# EasyEDA.net
KiCad netlist of a schematic drawn in EasyEDA
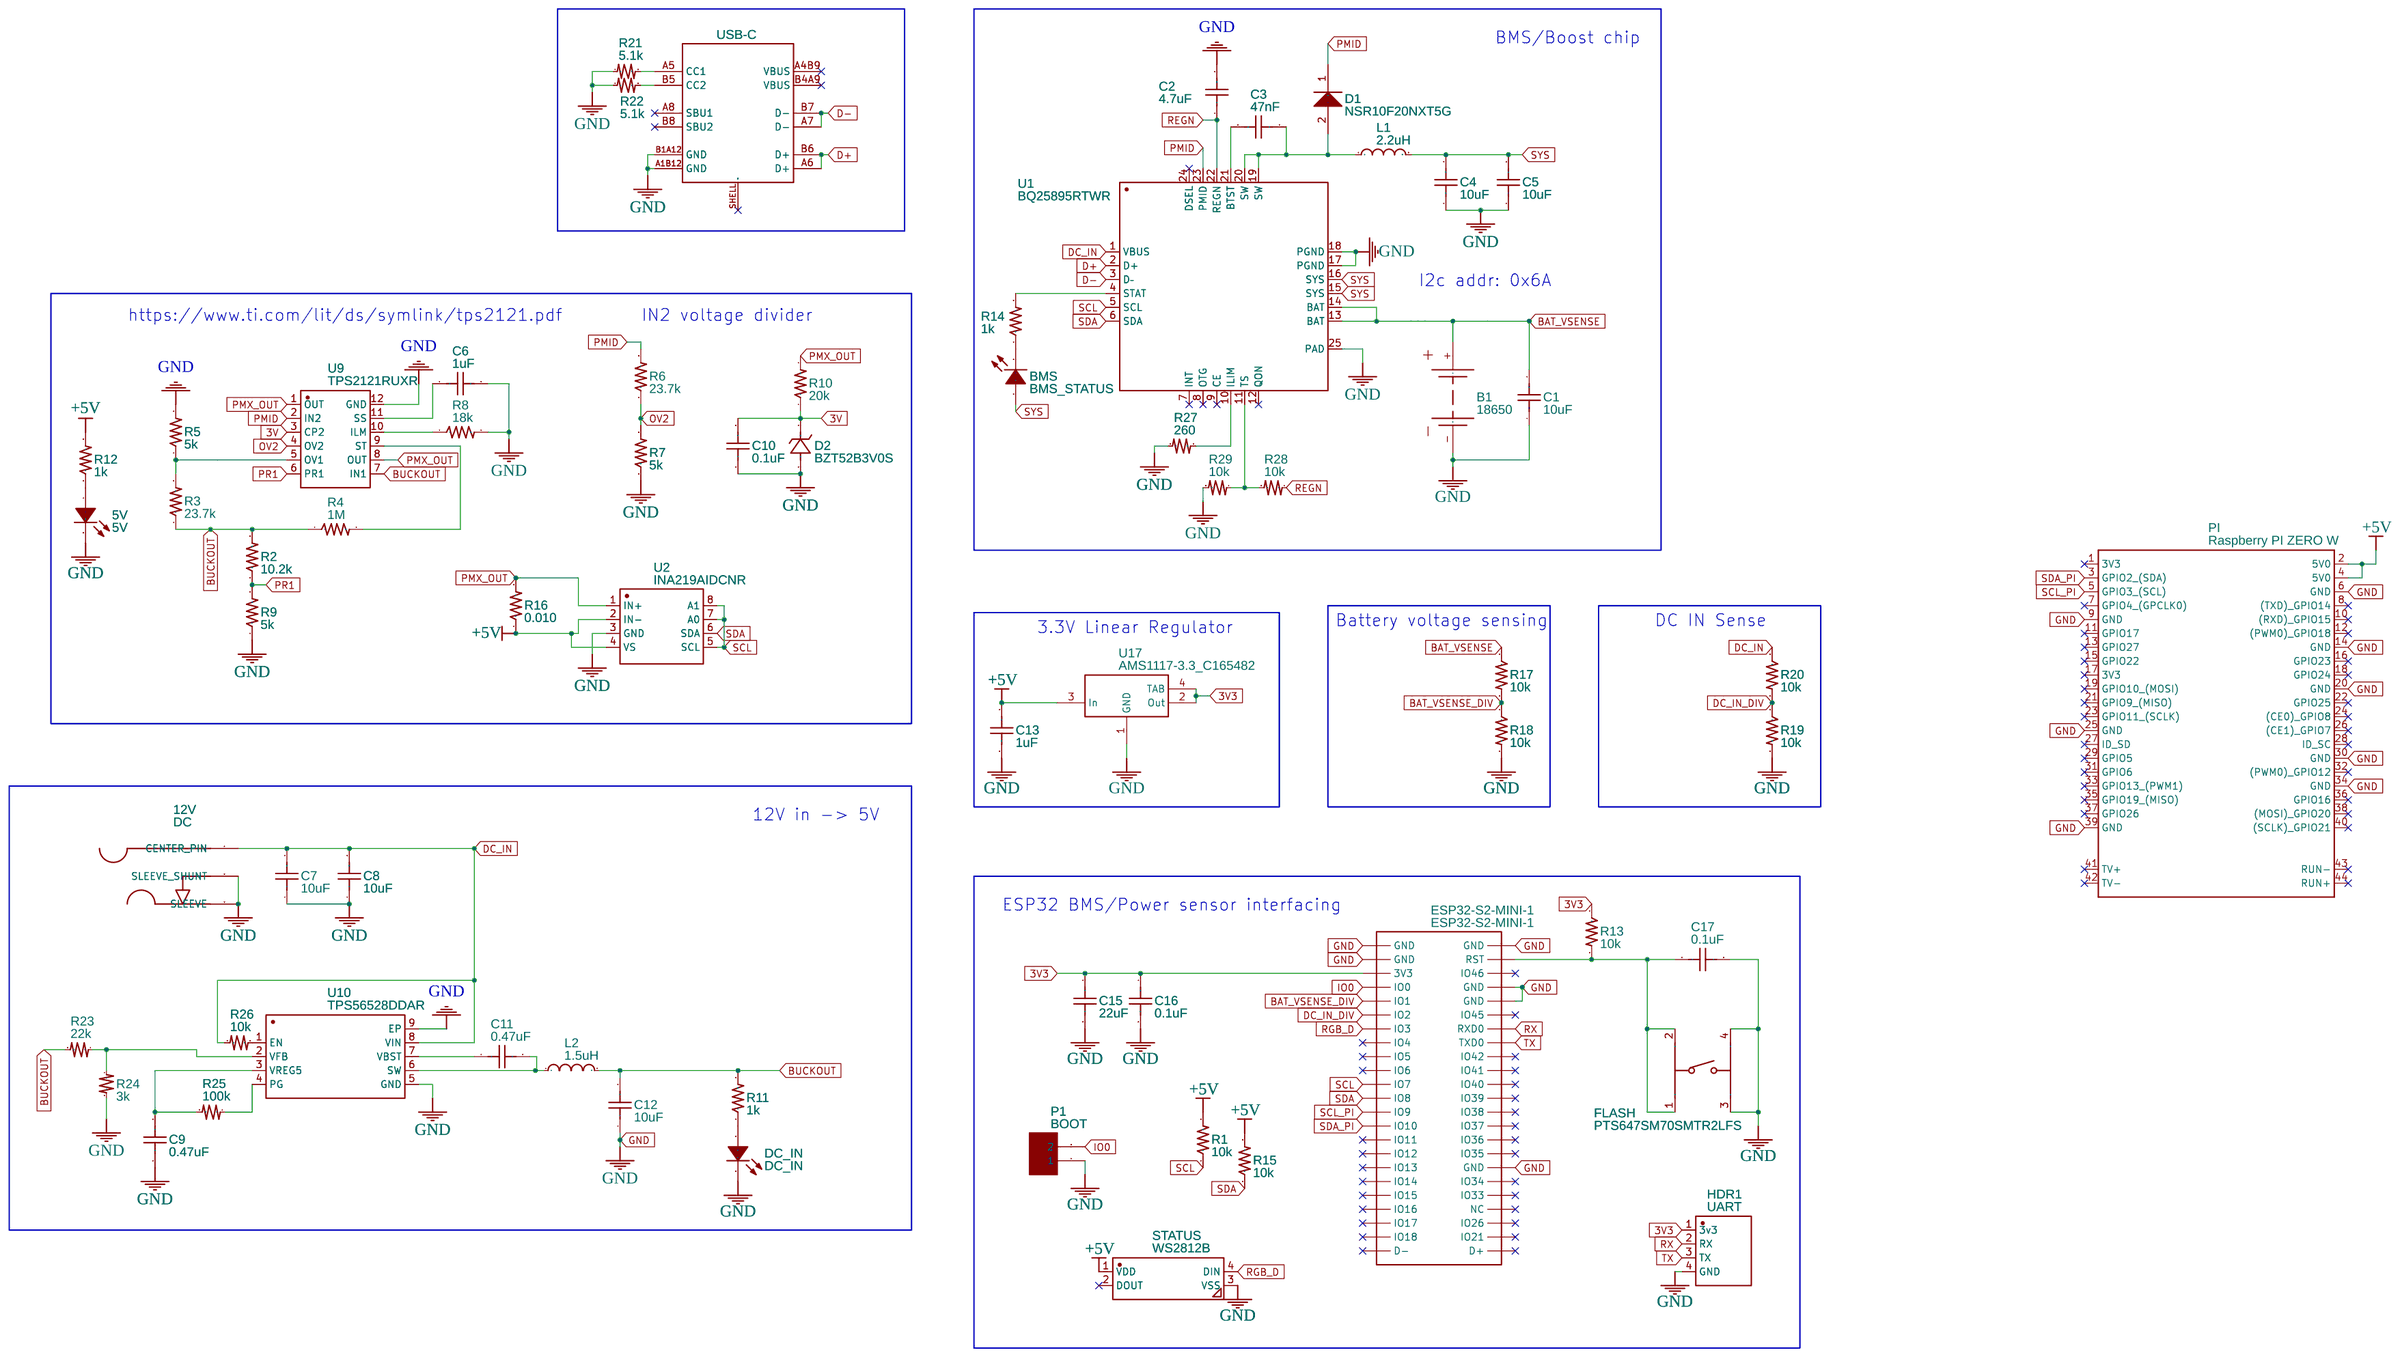
[diagram p0: schematic sheet]

(export (version "E")
  (design (tool "Eeschema 10.0.6"))
  (components
    (comp (ref "5V")
      (value "5V")
      (fields
        (field (name "BOM_Manufacturer Part") "E6C0805URAC1UDA")
        (field (name "BOM_Supplier Part") "C375451")
      )
      (libsource (lib "") (part "0805 LED_2"))
    )
    (comp (ref "12V") (value "DC") (libsource (lib "") (part "RASM712BKZ")))
    (comp (ref "B1") (value "18650") (libsource (lib "") (part "18650")))
    (comp (ref "BMS")
      (value "BMS_STATUS")
      (fields
        (field (name "BOM_Manufacturer Part") "E6C0805URAC1UDA")
        (field (name "BOM_Supplier Part") "C375451")
      )
      (libsource (lib "") (part "0805 LED"))
    )
    (comp (ref "C1")
      (value "10uF")
      (fields
        (field (name "BOM_Manufacturer Part") "0603ZD106KAT2A")
        (field (name "BOM_Supplier Part") "C2167556")
      )
      (libsource (lib "") (part "0603ZD106KAT2A_1"))
    )
    (comp (ref "C2")
      (value "4.7uF")
      (fields
        (field (name "BOM_Manufacturer Part") "0603ZD106KAT2A")
        (field (name "BOM_Supplier Part") "C2167556")
      )
      (libsource (lib "") (part "0603ZD106KAT2A_1"))
    )
    (comp (ref "C3")
      (value "47nF")
      (fields
        (field (name "BOM_Manufacturer Part") "0603ZD106KAT2A")
        (field (name "BOM_Supplier Part") "C2167556")
      )
      (libsource (lib "") (part "0603ZD106KAT2A_3"))
    )
    (comp (ref "C4")
      (value "10uF")
      (fields
        (field (name "BOM_Manufacturer Part") "0603ZD106KAT2A")
        (field (name "BOM_Supplier Part") "C2167556")
      )
      (libsource (lib "") (part "0603ZD106KAT2A_1"))
    )
    (comp (ref "C5")
      (value "10uF")
      (fields
        (field (name "BOM_Manufacturer Part") "0603ZD106KAT2A")
        (field (name "BOM_Supplier Part") "C2167556")
      )
      (libsource (lib "") (part "0603ZD106KAT2A_1"))
    )
    (comp (ref "C6")
      (value "1uF")
      (fields
        (field (name "BOM_Manufacturer Part") "0603ZD106KAT2A")
        (field (name "BOM_Supplier Part") "C2167556")
      )
      (libsource (lib "") (part "0603ZD106KAT2A"))
    )
    (comp (ref "C7")
      (value "10uF")
      (fields
        (field (name "BOM_Manufacturer Part") "0603ZD106KAT2A")
        (field (name "BOM_Supplier Part") "C2167556")
      )
      (libsource (lib "") (part "0603ZD106KAT2A_1"))
    )
    (comp (ref "C8")
      (value "10uF")
      (fields
        (field (name "BOM_Manufacturer Part") "0603ZD106KAT2A")
        (field (name "BOM_Supplier Part") "C2167556")
      )
      (libsource (lib "") (part "0603ZD106KAT2A_1"))
    )
    (comp (ref "C9")
      (value "0.47uF")
      (fields
        (field (name "BOM_Manufacturer Part") "0603ZD106KAT2A")
        (field (name "BOM_Supplier Part") "C2167556")
      )
      (libsource (lib "") (part "0603ZD106KAT2A_1"))
    )
    (comp (ref "C10")
      (value "0.1uF")
      (fields
        (field (name "BOM_Manufacturer Part") "0603ZD106KAT2A")
        (field (name "BOM_Supplier Part") "C2167556")
      )
      (libsource (lib "") (part "0603ZD106KAT2A_1"))
    )
    (comp (ref "C11")
      (value "0.47uF")
      (fields
        (field (name "BOM_Manufacturer Part") "0603ZD106KAT2A")
        (field (name "BOM_Supplier Part") "C2167556")
      )
      (libsource (lib "") (part "0603ZD106KAT2A"))
    )
    (comp (ref "C12")
      (value "10uF")
      (fields
        (field (name "BOM_Manufacturer Part") "0603ZD106KAT2A")
        (field (name "BOM_Supplier Part") "C2167556")
      )
      (libsource (lib "") (part "0603ZD106KAT2A_1"))
    )
    (comp (ref "C13")
      (value "1uF")
      (fields
        (field (name "BOM_Manufacturer Part") "0603ZD106KAT2A")
        (field (name "BOM_Supplier Part") "C2167556")
      )
      (libsource (lib "") (part "0603ZD106KAT2A_2"))
    )
    (comp (ref "C15")
      (value "22uF")
      (fields
        (field (name "BOM_Manufacturer Part") "0603ZD106KAT2A")
        (field (name "BOM_Supplier Part") "C2167556")
      )
      (libsource (lib "") (part "0603ZD106KAT2A_2"))
    )
    (comp (ref "C16")
      (value "0.1uF")
      (fields
        (field (name "BOM_Manufacturer Part") "0603ZD106KAT2A")
        (field (name "BOM_Supplier Part") "C2167556")
      )
      (libsource (lib "") (part "0603ZD106KAT2A_2"))
    )
    (comp (ref "C17")
      (value "0.1uF")
      (fields
        (field (name "BOM_Manufacturer Part") "0603ZD106KAT2A")
        (field (name "BOM_Supplier Part") "C2167556")
      )
      (libsource (lib "") (part "0603ZD106KAT2A"))
    )
    (comp (ref "D1") (value "NSR10F20NXT5G") (libsource (lib "") (part "NSR10F20NXT5G")))
    (comp (ref "D2")
      (value "BZT52B3V0S")
      (fields (field (name "BOM_Supplier Part") "C699123"))
      (libsource (lib "") (part "BZT52B3V0S_C699123"))
    )
    (comp (ref "DC_IN")
      (value "DC_IN")
      (fields
        (field (name "BOM_Manufacturer Part") "E6C0805URAC1UDA")
        (field (name "BOM_Supplier Part") "C375451")
      )
      (libsource (lib "") (part "0805 LED_1"))
    )
    (comp (ref "ESP32-S2-MINI-1") (value "ESP32-S2-MINI-1") (libsource (lib "") (part "ESP32-S2-MINI-1")))
    (comp (ref "FLASH")
      (value "PTS647SM70SMTR2LFS")
      (fields (field (name "BOM_Supplier Part") "C2689517"))
      (libsource (lib "") (part "PTS647SM70SMTR2LFS"))
    )
    (comp (ref "HDR1")
      (value "UART")
      (fields
        (field (name "BOM_Manufacturer Part") "RE-H042TD-1190(LF)(SN)")
        (field (name "BOM_Supplier Part") "C265319")
      )
      (libsource (lib "") (part "RE-H042TD-1190(LF)(SN)"))
    )
    (comp (ref "L1")
      (value "2.2uH")
      (fields
        (field (name "BOM_Manufacturer Part") "36502AR36JTDG")
        (field (name "BOM_Supplier Part") "C1330274")
      )
      (libsource (lib "") (part "36502AR36JTDG"))
    )
    (comp (ref "L2")
      (value "1.5uH")
      (fields
        (field (name "BOM_Manufacturer Part") "YXMAC1040-1R5M-ITF")
        (field (name "BOM_Supplier Part") "C241406")
      )
      (libsource (lib "") (part "YXMAC1040-1R5M-ITF"))
    )
    (comp (ref "P1") (value "BOOT") (libsource (lib "") (part "HDR1X2")))
    (comp (ref "PI") (value "Raspberry PI ZERO W") (libsource (lib "") (part "Raspberry PI ZERO W")))
    (comp (ref "R1") (value "10k") (libsource (lib "") (part "0.22OHM-1_4W-1%(0805)_1")))
    (comp (ref "R2") (value "10.2k") (libsource (lib "") (part "0.22OHM-1_4W-1%(0805)_1")))
    (comp (ref "R3") (value "23.7k") (libsource (lib "") (part "0.22OHM-1_4W-1%(0805)_1")))
    (comp (ref "R4") (value "1M") (libsource (lib "") (part "0.22OHM-1_4W-1%(0805)_2")))
    (comp (ref "R5") (value "5k") (libsource (lib "") (part "0.22OHM-1_4W-1%(0805)_1")))
    (comp (ref "R6") (value "23.7k") (libsource (lib "") (part "0.22OHM-1_4W-1%(0805)_1")))
    (comp (ref "R7") (value "5k") (libsource (lib "") (part "0.22OHM-1_4W-1%(0805)_1")))
    (comp (ref "R8") (value "18k") (libsource (lib "") (part "0.22OHM-1_4W-1%(0805)_2")))
    (comp (ref "R9") (value "5k") (libsource (lib "") (part "0.22OHM-1_4W-1%(0805)_1")))
    (comp (ref "R10") (value "20k") (libsource (lib "") (part "0.22OHM-1_4W-1%(0805)_1")))
    (comp (ref "R11") (value "1k") (libsource (lib "") (part "0.22OHM-1_4W-1%(0805)_1")))
    (comp (ref "R12") (value "1k") (libsource (lib "") (part "0.22OHM-1_4W-1%(0805)_1")))
    (comp (ref "R13") (value "10k") (libsource (lib "") (part "0.22OHM-1_4W-1%(0805)")))
    (comp (ref "R14") (value "1k") (libsource (lib "") (part "0.22OHM-1_4W-1%(0805)_1")))
    (comp (ref "R15") (value "10k") (libsource (lib "") (part "0.22OHM-1_4W-1%(0805)_1")))
    (comp (ref "R16") (value "0.010") (libsource (lib "") (part "0.22OHM-1_4W-1%(0805)_1")))
    (comp (ref "R17") (value "10k") (libsource (lib "") (part "0.22OHM-1_4W-1%(0805)")))
    (comp (ref "R18") (value "10k") (libsource (lib "") (part "0.22OHM-1_4W-1%(0805)")))
    (comp (ref "R19") (value "10k") (libsource (lib "") (part "0.22OHM-1_4W-1%(0805)")))
    (comp (ref "R20") (value "10k") (libsource (lib "") (part "0.22OHM-1_4W-1%(0805)")))
    (comp (ref "R21") (value "5.1k") (libsource (lib "") (part "0805 Resistor_1")))
    (comp (ref "R22") (value "5.1k") (libsource (lib "") (part "0805 Resistor_1")))
    (comp (ref "R23") (value "22k") (libsource (lib "") (part "0805 Resistor")))
    (comp (ref "R24") (value "3k") (libsource (lib "") (part "0805 Resistor_2")))
    (comp (ref "R25") (value "100k") (libsource (lib "") (part "0805 Resistor")))
    (comp (ref "R26") (value "10k") (libsource (lib "") (part "0805 Resistor")))
    (comp (ref "R27") (value "260") (libsource (lib "") (part "0805 Resistor_1")))
    (comp (ref "R28") (value "10k") (libsource (lib "") (part "0805 Resistor")))
    (comp (ref "R29") (value "10k") (libsource (lib "") (part "0805 Resistor")))
    (comp (ref "STATUS")
      (value "WS2812B")
      (fields (field (name "BOM_Supplier Part") "C114585"))
      (libsource (lib "") (part "WS2812B"))
    )
    (comp (ref "U1")
      (value "BQ25895RTWR")
      (fields (field (name "BOM_Supplier Part") "C80200"))
      (libsource (lib "") (part "BQ25895RTWR"))
    )
    (comp (ref "U2")
      (value "INA219AIDCNR")
      (fields (field (name "BOM_Supplier Part") "C87469"))
      (libsource (lib "") (part "INA219AIDCNR"))
    )
    (comp (ref "U9")
      (value "TPS2121RUXR")
      (fields (field (name "BOM_Supplier Part") "C485916"))
      (libsource (lib "") (part "TPS2121RUXR"))
    )
    (comp (ref "U10")
      (value "TPS56528DDAR")
      (fields (field (name "BOM_Supplier Part") "C138716"))
      (libsource (lib "") (part "TPS56528DDAR"))
    )
    (comp (ref "U17")
      (value "AMS1117-3.3_C165482")
      (fields
        (field (name "BOM_Manufacturer Part") "AMS1117-3.3")
        (field (name "BOM_Supplier Part") "C165482")
      )
      (libsource (lib "") (part "AMS1117-3.3_C165482"))
    )
    (comp (ref "VBUS")
      (value "USB-C")
      (fields
        (field (name "BOM_Manufacturer Part") "XKB Enterprise")
        (field (name "BOM_Supplier Part") "C319148")
      )
      (libsource (lib "") (part "USB-C"))
    )
  )
  (nets
    (net (code "1") (name "+5V") (class "Default")
      (node (ref "C13") (pin "1") (pinfunction "1_1") (pintype "unspecified"))
      (node (ref "PI") (pin "2") (pinfunction "5V0_2") (pintype "unspecified"))
      (node (ref "PI") (pin "4") (pinfunction "5V0_4") (pintype "unspecified"))
      (node (ref "R1") (pin "2") (pinfunction "2_2") (pintype "unspecified"))
      (node (ref "R12") (pin "2") (pinfunction "2_2") (pintype "unspecified"))
      (node (ref "R15") (pin "2") (pinfunction "2_2") (pintype "unspecified"))
      (node (ref "R16") (pin "1") (pinfunction "1_1") (pintype "unspecified"))
      (node (ref "STATUS") (pin "1") (pinfunction "VDD_1") (pintype "unspecified"))
      (node (ref "U17") (pin "3") (pinfunction "In_3") (pintype "unspecified"))
      (node (ref "U2") (pin "2") (pinfunction "IN-_2") (pintype "unspecified"))
      (node (ref "U2") (pin "4") (pinfunction "VS_4") (pintype "unspecified"))
    )
    (net (code "2") (name "3V") (class "Default")
      (node (ref "C10") (pin "2") (pinfunction "2_2") (pintype "unspecified"))
      (node (ref "D2") (pin "1") (pinfunction "C_1") (pintype "unspecified"))
      (node (ref "R10") (pin "1") (pinfunction "1_1") (pintype "unspecified"))
      (node (ref "U9") (pin "3") (pinfunction "CP2_3") (pintype "unspecified"))
    )
    (net (code "3") (name "3V3") (class "Default")
      (node (ref "C15") (pin "1") (pinfunction "1_1") (pintype "unspecified"))
      (node (ref "C16") (pin "1") (pinfunction "1_1") (pintype "unspecified"))
      (node (ref "ESP32-S2-MINI-1") (pin "3") (pinfunction "3V3_3") (pintype "unspecified"))
      (node (ref "HDR1") (pin "1") (pinfunction "3v3_1") (pintype "unspecified"))
      (node (ref "R13") (pin "1") (pinfunction "1_1") (pintype "unspecified"))
      (node (ref "U17") (pin "2") (pinfunction "Out_2") (pintype "unspecified"))
      (node (ref "U17") (pin "4") (pinfunction "TAB_4") (pintype "unspecified"))
    )
    (net (code "4") (name "BAT_VSENSE") (class "Default")
      (node (ref "B1") (pin "+") (pinfunction "1_+") (pintype "unspecified"))
      (node (ref "C1") (pin "2") (pinfunction "2_2") (pintype "unspecified"))
      (node (ref "R17") (pin "1") (pinfunction "1_1") (pintype "unspecified"))
      (node (ref "U1") (pin "13") (pinfunction "BAT_13") (pintype "unspecified"))
      (node (ref "U1") (pin "14") (pinfunction "BAT_14") (pintype "unspecified"))
    )
    (net (code "5") (name "BAT_VSENSE_DIV") (class "Default")
      (node (ref "ESP32-S2-MINI-1") (pin "5") (pinfunction "IO1_5") (pintype "unspecified"))
      (node (ref "R17") (pin "2") (pinfunction "2_2") (pintype "unspecified"))
      (node (ref "R18") (pin "1") (pinfunction "1_1") (pintype "unspecified"))
    )
    (net (code "6") (name "BUCKOUT") (class "Default")
      (node (ref "C12") (pin "2") (pinfunction "2_2") (pintype "unspecified"))
      (node (ref "L2") (pin "2") (pinfunction "2_2") (pintype "unspecified"))
      (node (ref "R11") (pin "2") (pinfunction "2_2") (pintype "unspecified"))
      (node (ref "R2") (pin "2") (pinfunction "2_2") (pintype "unspecified"))
      (node (ref "R23") (pin "2") (pinfunction "2_2") (pintype "unspecified"))
      (node (ref "R3") (pin "1") (pinfunction "1_1") (pintype "unspecified"))
      (node (ref "R4") (pin "1") (pinfunction "1_1") (pintype "unspecified"))
      (node (ref "U9") (pin "7") (pinfunction "IN1_7") (pintype "unspecified"))
    )
    (net (code "7") (name "D+") (class "Default")
      (node (ref "U1") (pin "2") (pinfunction "D+_2") (pintype "unspecified"))
      (node (ref "VBUS") (pin "A6") (pinfunction "D+_A6") (pintype "unspecified"))
      (node (ref "VBUS") (pin "B6") (pinfunction "D+_B6") (pintype "unspecified"))
    )
    (net (code "8") (name "D-") (class "Default")
      (node (ref "U1") (pin "3") (pinfunction "D–_3") (pintype "unspecified"))
      (node (ref "VBUS") (pin "A7") (pinfunction "D-_A7") (pintype "unspecified"))
      (node (ref "VBUS") (pin "B7") (pinfunction "D-_B7") (pintype "unspecified"))
    )
    (net (code "9") (name "DC_IN") (class "Default")
      (node (ref "12V") (pin "1") (pinfunction "CENTER_PIN_1") (pintype "unspecified"))
      (node (ref "C7") (pin "2") (pinfunction "2_2") (pintype "unspecified"))
      (node (ref "C8") (pin "2") (pinfunction "2_2") (pintype "unspecified"))
      (node (ref "R20") (pin "1") (pinfunction "1_1") (pintype "unspecified"))
      (node (ref "R26") (pin "2") (pinfunction "2_2") (pintype "unspecified"))
      (node (ref "U1") (pin "1") (pinfunction "VBUS_1") (pintype "unspecified"))
      (node (ref "U10") (pin "8") (pinfunction "VIN_8") (pintype "unspecified"))
    )
    (net (code "10") (name "DC_IN_DIV") (class "Default")
      (node (ref "ESP32-S2-MINI-1") (pin "6") (pinfunction "IO2_6") (pintype "unspecified"))
      (node (ref "R19") (pin "1") (pinfunction "1_1") (pintype "unspecified"))
      (node (ref "R20") (pin "2") (pinfunction "2_2") (pintype "unspecified"))
    )
    (net (code "11") (name "GND") (class "Default")
      (node (ref "12V") (pin "2") (pinfunction "SLEEVE_SHUNT_2") (pintype "unspecified"))
      (node (ref "12V") (pin "3") (pinfunction "SLEEVE_3") (pintype "unspecified"))
      (node (ref "5V") (pin "2") (pinfunction "K_2") (pintype "unspecified"))
      (node (ref "B1") (pin "-") (pinfunction "2_-") (pintype "unspecified"))
      (node (ref "C1") (pin "1") (pinfunction "1_1") (pintype "unspecified"))
      (node (ref "C10") (pin "1") (pinfunction "1_1") (pintype "unspecified"))
      (node (ref "C12") (pin "1") (pinfunction "1_1") (pintype "unspecified"))
      (node (ref "C13") (pin "2") (pinfunction "2_2") (pintype "unspecified"))
      (node (ref "C15") (pin "2") (pinfunction "2_2") (pintype "unspecified"))
      (node (ref "C16") (pin "2") (pinfunction "2_2") (pintype "unspecified"))
      (node (ref "C17") (pin "2") (pinfunction "2_2") (pintype "unspecified"))
      (node (ref "C2") (pin "2") (pinfunction "2_2") (pintype "unspecified"))
      (node (ref "C4") (pin "1") (pinfunction "1_1") (pintype "unspecified"))
      (node (ref "C5") (pin "1") (pinfunction "1_1") (pintype "unspecified"))
      (node (ref "C6") (pin "2") (pinfunction "2_2") (pintype "unspecified"))
      (node (ref "C7") (pin "1") (pinfunction "1_1") (pintype "unspecified"))
      (node (ref "C8") (pin "1") (pinfunction "1_1") (pintype "unspecified"))
      (node (ref "C9") (pin "1") (pinfunction "1_1") (pintype "unspecified"))
      (node (ref "D2") (pin "2") (pinfunction "A_2") (pintype "unspecified"))
      (node (ref "DC_IN") (pin "2") (pinfunction "K_2") (pintype "unspecified"))
      (node (ref "ESP32-S2-MINI-1") (pin "GND") (pinfunction "GND_GND") (pintype "unspecified"))
      (node (ref "FLASH") (pin "3") (pinfunction "3_3") (pintype "unspecified"))
      (node (ref "FLASH") (pin "4") (pinfunction "4_4") (pintype "unspecified"))
      (node (ref "HDR1") (pin "4") (pinfunction "GND_4") (pintype "unspecified"))
      (node (ref "P1") (pin "1") (pinfunction "1_1") (pintype "unspecified"))
      (node (ref "PI") (pin "14") (pinfunction "GND_14") (pintype "unspecified"))
      (node (ref "PI") (pin "20") (pinfunction "GND_20") (pintype "unspecified"))
      (node (ref "PI") (pin "25") (pinfunction "GND_25") (pintype "unspecified"))
      (node (ref "PI") (pin "30") (pinfunction "GND_30") (pintype "unspecified"))
      (node (ref "PI") (pin "34") (pinfunction "GND_34") (pintype "unspecified"))
      (node (ref "PI") (pin "39") (pinfunction "GND_39") (pintype "unspecified"))
      (node (ref "PI") (pin "6") (pinfunction "GND_6") (pintype "unspecified"))
      (node (ref "PI") (pin "9") (pinfunction "GND_9") (pintype "unspecified"))
      (node (ref "R18") (pin "2") (pinfunction "2_2") (pintype "unspecified"))
      (node (ref "R19") (pin "2") (pinfunction "2_2") (pintype "unspecified"))
      (node (ref "R21") (pin "1") (pinfunction "1_1") (pintype "unspecified"))
      (node (ref "R22") (pin "1") (pinfunction "1_1") (pintype "unspecified"))
      (node (ref "R24") (pin "2") (pinfunction "2_2") (pintype "unspecified"))
      (node (ref "R27") (pin "1") (pinfunction "1_1") (pintype "unspecified"))
      (node (ref "R29") (pin "2") (pinfunction "2_2") (pintype "unspecified"))
      (node (ref "R5") (pin "2") (pinfunction "2_2") (pintype "unspecified"))
      (node (ref "R7") (pin "1") (pinfunction "1_1") (pintype "unspecified"))
      (node (ref "R8") (pin "2") (pinfunction "2_2") (pintype "unspecified"))
      (node (ref "R9") (pin "1") (pinfunction "1_1") (pintype "unspecified"))
      (node (ref "STATUS") (pin "3") (pinfunction "VSS_3") (pintype "unspecified"))
      (node (ref "U1") (pin "17") (pinfunction "PGND_17") (pintype "unspecified"))
      (node (ref "U1") (pin "18") (pinfunction "PGND_18") (pintype "unspecified"))
      (node (ref "U1") (pin "25") (pinfunction "PAD_25") (pintype "unspecified"))
      (node (ref "U10") (pin "5") (pinfunction "GND_5") (pintype "unspecified"))
      (node (ref "U10") (pin "9") (pinfunction "EP_9") (pintype "unspecified"))
      (node (ref "U17") (pin "1") (pinfunction "GND_1") (pintype "unspecified"))
      (node (ref "U2") (pin "3") (pinfunction "GND_3") (pintype "unspecified"))
      (node (ref "U9") (pin "12") (pinfunction "GND_12") (pintype "unspecified"))
      (node (ref "VBUS") (pin "A1B12") (pinfunction "GND_A1B12") (pintype "unspecified"))
      (node (ref "VBUS") (pin "B1A12") (pinfunction "GND_B1A12") (pintype "unspecified"))
    )
    (net (code "12") (name "IO0") (class "Default")
      (node (ref "ESP32-S2-MINI-1") (pin "4") (pinfunction "IO0_4") (pintype "unspecified"))
      (node (ref "P1") (pin "2") (pinfunction "2_2") (pintype "unspecified"))
    )
    (net (code "13") (name "Net-(5V-A)") (class "Default")
      (node (ref "5V") (pin "1") (pinfunction "A_1") (pintype "unspecified"))
      (node (ref "R12") (pin "1") (pinfunction "1_1") (pintype "unspecified"))
    )
    (net (code "14") (name "Net-(BMS-K)") (class "Default")
      (node (ref "BMS") (pin "2") (pinfunction "K_2") (pintype "unspecified"))
      (node (ref "R14") (pin "1") (pinfunction "1_1") (pintype "unspecified"))
    )
    (net (code "15") (name "Net-(D1-A)") (class "Default")
      (node (ref "C3") (pin "1") (pinfunction "1_1") (pintype "unspecified"))
      (node (ref "D1") (pin "2") (pinfunction "A_2") (pintype "unspecified"))
      (node (ref "L1") (pin "1") (pinfunction "1_1") (pintype "unspecified"))
      (node (ref "U1") (pin "19") (pinfunction "SW_19") (pintype "unspecified"))
      (node (ref "U1") (pin "20") (pinfunction "SW_20") (pintype "unspecified"))
    )
    (net (code "16") (name "Net-(DC_IN-A)") (class "Default")
      (node (ref "DC_IN") (pin "1") (pinfunction "A_1") (pintype "unspecified"))
      (node (ref "R11") (pin "1") (pinfunction "1_1") (pintype "unspecified"))
    )
    (net (code "17") (name "Net-(ESP32-S2-MINI-1-RST)") (class "Default")
      (node (ref "C17") (pin "1") (pinfunction "1_1") (pintype "unspecified"))
      (node (ref "ESP32-S2-MINI-1") (pin "45") (pinfunction "RST_45") (pintype "unspecified"))
      (node (ref "FLASH") (pin "1") (pinfunction "1_1") (pintype "unspecified"))
      (node (ref "FLASH") (pin "2") (pinfunction "2_2") (pintype "unspecified"))
      (node (ref "R13") (pin "2") (pinfunction "2_2") (pintype "unspecified"))
    )
    (net (code "18") (name "Net-(U1-BTST)") (class "Default")
      (node (ref "C3") (pin "2") (pinfunction "2_2") (pintype "unspecified"))
      (node (ref "U1") (pin "21") (pinfunction "BTST_21") (pintype "unspecified"))
    )
    (net (code "19") (name "Net-(U1-ILIM)") (class "Default")
      (node (ref "R27") (pin "2") (pinfunction "2_2") (pintype "unspecified"))
      (node (ref "U1") (pin "10") (pinfunction "ILIM_10") (pintype "unspecified"))
    )
    (net (code "20") (name "Net-(U1-STAT)") (class "Default")
      (node (ref "R14") (pin "2") (pinfunction "2_2") (pintype "unspecified"))
      (node (ref "U1") (pin "4") (pinfunction "STAT_4") (pintype "unspecified"))
    )
    (net (code "21") (name "Net-(U1-TS)") (class "Default")
      (node (ref "R28") (pin "2") (pinfunction "2_2") (pintype "unspecified"))
      (node (ref "R29") (pin "1") (pinfunction "1_1") (pintype "unspecified"))
      (node (ref "U1") (pin "11") (pinfunction "TS_11") (pintype "unspecified"))
    )
    (net (code "22") (name "Net-(U9-ILM)") (class "Default")
      (node (ref "R8") (pin "1") (pinfunction "1_1") (pintype "unspecified"))
      (node (ref "U9") (pin "10") (pinfunction "ILM_10") (pintype "unspecified"))
    )
    (net (code "23") (name "Net-(U9-OV1)") (class "Default")
      (node (ref "R3") (pin "2") (pinfunction "2_2") (pintype "unspecified"))
      (node (ref "R5") (pin "1") (pinfunction "1_1") (pintype "unspecified"))
      (node (ref "U9") (pin "5") (pinfunction "OV1_5") (pintype "unspecified"))
    )
    (net (code "24") (name "Net-(U9-SS)") (class "Default")
      (node (ref "C6") (pin "1") (pinfunction "1_1") (pintype "unspecified"))
      (node (ref "U9") (pin "11") (pinfunction "SS_11") (pintype "unspecified"))
    )
    (net (code "25") (name "Net-(U9-ST)") (class "Default")
      (node (ref "R4") (pin "2") (pinfunction "2_2") (pintype "unspecified"))
      (node (ref "U9") (pin "9") (pinfunction "ST_9") (pintype "unspecified"))
    )
    (net (code "26") (name "Net-(U10-EN)") (class "Default")
      (node (ref "R26") (pin "1") (pinfunction "1_1") (pintype "unspecified"))
      (node (ref "U10") (pin "1") (pinfunction "EN_1") (pintype "unspecified"))
    )
    (net (code "27") (name "Net-(U10-PG)") (class "Default")
      (node (ref "R25") (pin "1") (pinfunction "1_1") (pintype "unspecified"))
      (node (ref "U10") (pin "4") (pinfunction "PG_4") (pintype "unspecified"))
    )
    (net (code "28") (name "Net-(U10-SW)") (class "Default")
      (node (ref "C11") (pin "2") (pinfunction "2_2") (pintype "unspecified"))
      (node (ref "L2") (pin "1") (pinfunction "1_1") (pintype "unspecified"))
      (node (ref "U10") (pin "6") (pinfunction "SW_6") (pintype "unspecified"))
    )
    (net (code "29") (name "Net-(U10-VBST)") (class "Default")
      (node (ref "C11") (pin "1") (pinfunction "1_1") (pintype "unspecified"))
      (node (ref "U10") (pin "7") (pinfunction "VBST_7") (pintype "unspecified"))
    )
    (net (code "30") (name "Net-(U10-VFB)") (class "Default")
      (node (ref "R23") (pin "1") (pinfunction "1_1") (pintype "unspecified"))
      (node (ref "R24") (pin "1") (pinfunction "1_1") (pintype "unspecified"))
      (node (ref "U10") (pin "2") (pinfunction "VFB_2") (pintype "unspecified"))
    )
    (net (code "31") (name "Net-(U10-VREG5)") (class "Default")
      (node (ref "C9") (pin "2") (pinfunction "2_2") (pintype "unspecified"))
      (node (ref "R25") (pin "2") (pinfunction "2_2") (pintype "unspecified"))
      (node (ref "U10") (pin "3") (pinfunction "VREG5_3") (pintype "unspecified"))
    )
    (net (code "32") (name "Net-(VBUS-CC1)") (class "Default")
      (node (ref "R21") (pin "2") (pinfunction "2_2") (pintype "unspecified"))
      (node (ref "VBUS") (pin "A5") (pinfunction "CC1_A5") (pintype "unspecified"))
    )
    (net (code "33") (name "Net-(VBUS-CC2)") (class "Default")
      (node (ref "R22") (pin "2") (pinfunction "2_2") (pintype "unspecified"))
      (node (ref "VBUS") (pin "B5") (pinfunction "CC2_B5") (pintype "unspecified"))
    )
    (net (code "34") (name "OV2") (class "Default")
      (node (ref "R6") (pin "1") (pinfunction "1_1") (pintype "unspecified"))
      (node (ref "R7") (pin "2") (pinfunction "2_2") (pintype "unspecified"))
      (node (ref "U9") (pin "4") (pinfunction "OV2_4") (pintype "unspecified"))
    )
    (net (code "35") (name "PMID") (class "Default")
      (node (ref "D1") (pin "1") (pinfunction "K_1") (pintype "unspecified"))
      (node (ref "R6") (pin "2") (pinfunction "2_2") (pintype "unspecified"))
      (node (ref "U1") (pin "23") (pinfunction "PMID_23") (pintype "unspecified"))
      (node (ref "U9") (pin "2") (pinfunction "IN2_2") (pintype "unspecified"))
    )
    (net (code "36") (name "PMX_OUT") (class "Default")
      (node (ref "R10") (pin "2") (pinfunction "2_2") (pintype "unspecified"))
      (node (ref "R16") (pin "2") (pinfunction "2_2") (pintype "unspecified"))
      (node (ref "U2") (pin "1") (pinfunction "IN+_1") (pintype "unspecified"))
      (node (ref "U9") (pin "1") (pinfunction "OUT_1") (pintype "unspecified"))
      (node (ref "U9") (pin "8") (pinfunction "OUT_8") (pintype "unspecified"))
    )
    (net (code "37") (name "PR1") (class "Default")
      (node (ref "R2") (pin "1") (pinfunction "1_1") (pintype "unspecified"))
      (node (ref "R9") (pin "2") (pinfunction "2_2") (pintype "unspecified"))
      (node (ref "U9") (pin "6") (pinfunction "PR1_6") (pintype "unspecified"))
    )
    (net (code "38") (name "REGN") (class "Default")
      (node (ref "C2") (pin "1") (pinfunction "1_1") (pintype "unspecified"))
      (node (ref "R28") (pin "1") (pinfunction "1_1") (pintype "unspecified"))
      (node (ref "U1") (pin "22") (pinfunction "REGN_22") (pintype "unspecified"))
    )
    (net (code "39") (name "RGB_D") (class "Default")
      (node (ref "ESP32-S2-MINI-1") (pin "7") (pinfunction "IO3_7") (pintype "unspecified"))
      (node (ref "STATUS") (pin "4") (pinfunction "DIN_4") (pintype "unspecified"))
    )
    (net (code "40") (name "RX") (class "Default")
      (node (ref "ESP32-S2-MINI-1") (pin "40") (pinfunction "RXD0_40") (pintype "unspecified"))
      (node (ref "HDR1") (pin "2") (pinfunction "RX_2") (pintype "unspecified"))
    )
    (net (code "41") (name "SCL") (class "Default")
      (node (ref "ESP32-S2-MINI-1") (pin "11") (pinfunction "IO7_11") (pintype "unspecified"))
      (node (ref "R1") (pin "1") (pinfunction "1_1") (pintype "unspecified"))
      (node (ref "U1") (pin "5") (pinfunction "SCL_5") (pintype "unspecified"))
      (node (ref "U2") (pin "5") (pinfunction "SCL_5") (pintype "unspecified"))
      (node (ref "U2") (pin "7") (pinfunction "A0_7") (pintype "unspecified"))
      (node (ref "U2") (pin "8") (pinfunction "A1_8") (pintype "unspecified"))
    )
    (net (code "42") (name "SCL_PI") (class "Default")
      (node (ref "ESP32-S2-MINI-1") (pin "13") (pinfunction "IO9_13") (pintype "unspecified"))
      (node (ref "PI") (pin "5") (pinfunction "GPIO3_(SCL)_5") (pintype "unspecified"))
    )
    (net (code "43") (name "SDA") (class "Default")
      (node (ref "ESP32-S2-MINI-1") (pin "12") (pinfunction "IO8_12") (pintype "unspecified"))
      (node (ref "R15") (pin "1") (pinfunction "1_1") (pintype "unspecified"))
      (node (ref "U1") (pin "6") (pinfunction "SDA_6") (pintype "unspecified"))
      (node (ref "U2") (pin "6") (pinfunction "SDA_6") (pintype "unspecified"))
    )
    (net (code "44") (name "SDA_PI") (class "Default")
      (node (ref "ESP32-S2-MINI-1") (pin "14") (pinfunction "IO10_14") (pintype "unspecified"))
      (node (ref "PI") (pin "3") (pinfunction "GPIO2_(SDA)_3") (pintype "unspecified"))
    )
    (net (code "45") (name "SYS") (class "Default")
      (node (ref "BMS") (pin "1") (pinfunction "A_1") (pintype "unspecified"))
      (node (ref "C4") (pin "2") (pinfunction "2_2") (pintype "unspecified"))
      (node (ref "C5") (pin "2") (pinfunction "2_2") (pintype "unspecified"))
      (node (ref "L1") (pin "2") (pinfunction "2_2") (pintype "unspecified"))
      (node (ref "U1") (pin "15") (pinfunction "SYS_15") (pintype "unspecified"))
      (node (ref "U1") (pin "16") (pinfunction "SYS_16") (pintype "unspecified"))
    )
    (net (code "46") (name "TX") (class "Default")
      (node (ref "ESP32-S2-MINI-1") (pin "39") (pinfunction "TXD0_39") (pintype "unspecified"))
      (node (ref "HDR1") (pin "3") (pinfunction "TX_3") (pintype "unspecified"))
    )
    (net (code "47") (name "unconnected-(ESP32-S2-MINI-1-D+-Pad24)") (class "Default")
      (node (ref "ESP32-S2-MINI-1") (pin "24") (pinfunction "D+_24") (pintype "unspecified+no_connect"))
    )
    (net (code "48") (name "unconnected-(ESP32-S2-MINI-1-D--Pad23)") (class "Default")
      (node (ref "ESP32-S2-MINI-1") (pin "23") (pinfunction "D-_23") (pintype "unspecified+no_connect"))
    )
    (net (code "49") (name "unconnected-(ESP32-S2-MINI-1-IO4-Pad8)") (class "Default")
      (node (ref "ESP32-S2-MINI-1") (pin "8") (pinfunction "IO4_8") (pintype "unspecified+no_connect"))
    )
    (net (code "50") (name "unconnected-(ESP32-S2-MINI-1-IO5-Pad9)") (class "Default")
      (node (ref "ESP32-S2-MINI-1") (pin "9") (pinfunction "IO5_9") (pintype "unspecified+no_connect"))
    )
    (net (code "51") (name "unconnected-(ESP32-S2-MINI-1-IO6-Pad10)") (class "Default")
      (node (ref "ESP32-S2-MINI-1") (pin "10") (pinfunction "IO6_10") (pintype "unspecified+no_connect"))
    )
    (net (code "52") (name "unconnected-(ESP32-S2-MINI-1-IO11-Pad15)") (class "Default")
      (node (ref "ESP32-S2-MINI-1") (pin "15") (pinfunction "IO11_15") (pintype "unspecified+no_connect"))
    )
    (net (code "53") (name "unconnected-(ESP32-S2-MINI-1-IO12-Pad16)") (class "Default")
      (node (ref "ESP32-S2-MINI-1") (pin "16") (pinfunction "IO12_16") (pintype "unspecified+no_connect"))
    )
    (net (code "54") (name "unconnected-(ESP32-S2-MINI-1-IO13-Pad17)") (class "Default")
      (node (ref "ESP32-S2-MINI-1") (pin "17") (pinfunction "IO13_17") (pintype "unspecified+no_connect"))
    )
    (net (code "55") (name "unconnected-(ESP32-S2-MINI-1-IO14-Pad18)") (class "Default")
      (node (ref "ESP32-S2-MINI-1") (pin "18") (pinfunction "IO14_18") (pintype "unspecified+no_connect"))
    )
    (net (code "56") (name "unconnected-(ESP32-S2-MINI-1-IO15-Pad19)") (class "Default")
      (node (ref "ESP32-S2-MINI-1") (pin "19") (pinfunction "IO15_19") (pintype "unspecified+no_connect"))
    )
    (net (code "57") (name "unconnected-(ESP32-S2-MINI-1-IO16-Pad20)") (class "Default")
      (node (ref "ESP32-S2-MINI-1") (pin "20") (pinfunction "IO16_20") (pintype "unspecified+no_connect"))
    )
    (net (code "58") (name "unconnected-(ESP32-S2-MINI-1-IO17-Pad21)") (class "Default")
      (node (ref "ESP32-S2-MINI-1") (pin "21") (pinfunction "IO17_21") (pintype "unspecified+no_connect"))
    )
    (net (code "59") (name "unconnected-(ESP32-S2-MINI-1-IO18-Pad22)") (class "Default")
      (node (ref "ESP32-S2-MINI-1") (pin "22") (pinfunction "IO18_22") (pintype "unspecified+no_connect"))
    )
    (net (code "60") (name "unconnected-(ESP32-S2-MINI-1-IO21-Pad25)") (class "Default")
      (node (ref "ESP32-S2-MINI-1") (pin "25") (pinfunction "IO21_25") (pintype "unspecified+no_connect"))
    )
    (net (code "61") (name "unconnected-(ESP32-S2-MINI-1-IO26-Pad26)") (class "Default")
      (node (ref "ESP32-S2-MINI-1") (pin "26") (pinfunction "IO26_26") (pintype "unspecified+no_connect"))
    )
    (net (code "62") (name "unconnected-(ESP32-S2-MINI-1-IO33-Pad28)") (class "Default")
      (node (ref "ESP32-S2-MINI-1") (pin "28") (pinfunction "IO33_28") (pintype "unspecified+no_connect"))
    )
    (net (code "63") (name "unconnected-(ESP32-S2-MINI-1-IO34-Pad29)") (class "Default")
      (node (ref "ESP32-S2-MINI-1") (pin "29") (pinfunction "IO34_29") (pintype "unspecified+no_connect"))
    )
    (net (code "64") (name "unconnected-(ESP32-S2-MINI-1-IO35-Pad31)") (class "Default")
      (node (ref "ESP32-S2-MINI-1") (pin "31") (pinfunction "IO35_31") (pintype "unspecified+no_connect"))
    )
    (net (code "65") (name "unconnected-(ESP32-S2-MINI-1-IO36-Pad32)") (class "Default")
      (node (ref "ESP32-S2-MINI-1") (pin "32") (pinfunction "IO36_32") (pintype "unspecified+no_connect"))
    )
    (net (code "66") (name "unconnected-(ESP32-S2-MINI-1-IO37-Pad33)") (class "Default")
      (node (ref "ESP32-S2-MINI-1") (pin "33") (pinfunction "IO37_33") (pintype "unspecified+no_connect"))
    )
    (net (code "67") (name "unconnected-(ESP32-S2-MINI-1-IO38-Pad34)") (class "Default")
      (node (ref "ESP32-S2-MINI-1") (pin "34") (pinfunction "IO38_34") (pintype "unspecified+no_connect"))
    )
    (net (code "68") (name "unconnected-(ESP32-S2-MINI-1-IO39-Pad35)") (class "Default")
      (node (ref "ESP32-S2-MINI-1") (pin "35") (pinfunction "IO39_35") (pintype "unspecified+no_connect"))
    )
    (net (code "69") (name "unconnected-(ESP32-S2-MINI-1-IO40-Pad36)") (class "Default")
      (node (ref "ESP32-S2-MINI-1") (pin "36") (pinfunction "IO40_36") (pintype "unspecified+no_connect"))
    )
    (net (code "70") (name "unconnected-(ESP32-S2-MINI-1-IO41-Pad37)") (class "Default")
      (node (ref "ESP32-S2-MINI-1") (pin "37") (pinfunction "IO41_37") (pintype "unspecified+no_connect"))
    )
    (net (code "71") (name "unconnected-(ESP32-S2-MINI-1-IO42-Pad38)") (class "Default")
      (node (ref "ESP32-S2-MINI-1") (pin "38") (pinfunction "IO42_38") (pintype "unspecified+no_connect"))
    )
    (net (code "72") (name "unconnected-(ESP32-S2-MINI-1-IO45-Pad41)") (class "Default")
      (node (ref "ESP32-S2-MINI-1") (pin "41") (pinfunction "IO45_41") (pintype "unspecified+no_connect"))
    )
    (net (code "73") (name "unconnected-(ESP32-S2-MINI-1-IO46-Pad44)") (class "Default")
      (node (ref "ESP32-S2-MINI-1") (pin "44") (pinfunction "IO46_44") (pintype "unspecified+no_connect"))
    )
    (net (code "74") (name "unconnected-(ESP32-S2-MINI-1-NC-Pad27)") (class "Default")
      (node (ref "ESP32-S2-MINI-1") (pin "27") (pinfunction "NC_27") (pintype "unspecified+no_connect"))
    )
    (net (code "75") (name "unconnected-(PI-(CE0)_GPIO8-Pad24)") (class "Default")
      (node (ref "PI") (pin "24") (pinfunction "(CE0)_GPIO8_24") (pintype "unspecified+no_connect"))
    )
    (net (code "76") (name "unconnected-(PI-(CE1)_GPIO7-Pad26)") (class "Default")
      (node (ref "PI") (pin "26") (pinfunction "(CE1)_GPIO7_26") (pintype "unspecified+no_connect"))
    )
    (net (code "77") (name "unconnected-(PI-(MOSI)_GPIO20-Pad38)") (class "Default")
      (node (ref "PI") (pin "38") (pinfunction "(MOSI)_GPIO20_38") (pintype "unspecified+no_connect"))
    )
    (net (code "78") (name "unconnected-(PI-(PWM0)_GPIO12-Pad32)") (class "Default")
      (node (ref "PI") (pin "32") (pinfunction "(PWM0)_GPIO12_32") (pintype "unspecified+no_connect"))
    )
    (net (code "79") (name "unconnected-(PI-(PWM0)_GPIO18-Pad12)") (class "Default")
      (node (ref "PI") (pin "12") (pinfunction "(PWM0)_GPIO18_12") (pintype "unspecified+no_connect"))
    )
    (net (code "80") (name "unconnected-(PI-(RXD)_GPIO15-Pad10)") (class "Default")
      (node (ref "PI") (pin "10") (pinfunction "(RXD)_GPIO15_10") (pintype "unspecified+no_connect"))
    )
    (net (code "81") (name "unconnected-(PI-(SCLK)_GPIO21-Pad40)") (class "Default")
      (node (ref "PI") (pin "40") (pinfunction "(SCLK)_GPIO21_40") (pintype "unspecified+no_connect"))
    )
    (net (code "82") (name "unconnected-(PI-(TXD)_GPIO14-Pad8)") (class "Default")
      (node (ref "PI") (pin "8") (pinfunction "(TXD)_GPIO14_8") (pintype "unspecified+no_connect"))
    )
    (net (code "83") (name "unconnected-(PI-3V3-Pad1)") (class "Default")
      (node (ref "PI") (pin "1") (pinfunction "3V3_1") (pintype "unspecified+no_connect"))
    )
    (net (code "84") (name "unconnected-(PI-3V3-Pad17)") (class "Default")
      (node (ref "PI") (pin "17") (pinfunction "3V3_17") (pintype "unspecified+no_connect"))
    )
    (net (code "85") (name "unconnected-(PI-GPIO4_(GPCLK0)-Pad7)") (class "Default")
      (node (ref "PI") (pin "7") (pinfunction "GPIO4_(GPCLK0)_7") (pintype "unspecified+no_connect"))
    )
    (net (code "86") (name "unconnected-(PI-GPIO5-Pad29)") (class "Default")
      (node (ref "PI") (pin "29") (pinfunction "GPIO5_29") (pintype "unspecified+no_connect"))
    )
    (net (code "87") (name "unconnected-(PI-GPIO6-Pad31)") (class "Default")
      (node (ref "PI") (pin "31") (pinfunction "GPIO6_31") (pintype "unspecified+no_connect"))
    )
    (net (code "88") (name "unconnected-(PI-GPIO9_(MISO)-Pad21)") (class "Default")
      (node (ref "PI") (pin "21") (pinfunction "GPIO9_(MISO)_21") (pintype "unspecified+no_connect"))
    )
    (net (code "89") (name "unconnected-(PI-GPIO10_(MOSI)-Pad19)") (class "Default")
      (node (ref "PI") (pin "19") (pinfunction "GPIO10_(MOSI)_19") (pintype "unspecified+no_connect"))
    )
    (net (code "90") (name "unconnected-(PI-GPIO11_(SCLK)-Pad23)") (class "Default")
      (node (ref "PI") (pin "23") (pinfunction "GPIO11_(SCLK)_23") (pintype "unspecified+no_connect"))
    )
    (net (code "91") (name "unconnected-(PI-GPIO13_(PWM1)-Pad33)") (class "Default")
      (node (ref "PI") (pin "33") (pinfunction "GPIO13_(PWM1)_33") (pintype "unspecified+no_connect"))
    )
    (net (code "92") (name "unconnected-(PI-GPIO16-Pad36)") (class "Default")
      (node (ref "PI") (pin "36") (pinfunction "GPIO16_36") (pintype "unspecified+no_connect"))
    )
    (net (code "93") (name "unconnected-(PI-GPIO17-Pad11)") (class "Default")
      (node (ref "PI") (pin "11") (pinfunction "GPIO17_11") (pintype "unspecified+no_connect"))
    )
    (net (code "94") (name "unconnected-(PI-GPIO19_(MISO)-Pad35)") (class "Default")
      (node (ref "PI") (pin "35") (pinfunction "GPIO19_(MISO)_35") (pintype "unspecified+no_connect"))
    )
    (net (code "95") (name "unconnected-(PI-GPIO22-Pad15)") (class "Default")
      (node (ref "PI") (pin "15") (pinfunction "GPIO22_15") (pintype "unspecified+no_connect"))
    )
    (net (code "96") (name "unconnected-(PI-GPIO23-Pad16)") (class "Default")
      (node (ref "PI") (pin "16") (pinfunction "GPIO23_16") (pintype "unspecified+no_connect"))
    )
    (net (code "97") (name "unconnected-(PI-GPIO24-Pad18)") (class "Default")
      (node (ref "PI") (pin "18") (pinfunction "GPIO24_18") (pintype "unspecified+no_connect"))
    )
    (net (code "98") (name "unconnected-(PI-GPIO25-Pad22)") (class "Default")
      (node (ref "PI") (pin "22") (pinfunction "GPIO25_22") (pintype "unspecified+no_connect"))
    )
    (net (code "99") (name "unconnected-(PI-GPIO26-Pad37)") (class "Default")
      (node (ref "PI") (pin "37") (pinfunction "GPIO26_37") (pintype "unspecified+no_connect"))
    )
    (net (code "100") (name "unconnected-(PI-GPIO27-Pad13)") (class "Default")
      (node (ref "PI") (pin "13") (pinfunction "GPIO27_13") (pintype "unspecified+no_connect"))
    )
    (net (code "101") (name "unconnected-(PI-ID_SC-Pad28)") (class "Default")
      (node (ref "PI") (pin "28") (pinfunction "ID_SC_28") (pintype "unspecified+no_connect"))
    )
    (net (code "102") (name "unconnected-(PI-ID_SD-Pad27)") (class "Default")
      (node (ref "PI") (pin "27") (pinfunction "ID_SD_27") (pintype "unspecified+no_connect"))
    )
    (net (code "103") (name "unconnected-(PI-RUN+-Pad44)") (class "Default")
      (node (ref "PI") (pin "44") (pinfunction "RUN+_44") (pintype "unspecified+no_connect"))
    )
    (net (code "104") (name "unconnected-(PI-RUN--Pad43)") (class "Default")
      (node (ref "PI") (pin "43") (pinfunction "RUN-_43") (pintype "unspecified+no_connect"))
    )
    (net (code "105") (name "unconnected-(PI-TV+-Pad41)") (class "Default")
      (node (ref "PI") (pin "41") (pinfunction "TV+_41") (pintype "unspecified+no_connect"))
    )
    (net (code "106") (name "unconnected-(PI-TV--Pad42)") (class "Default")
      (node (ref "PI") (pin "42") (pinfunction "TV-_42") (pintype "unspecified+no_connect"))
    )
    (net (code "107") (name "unconnected-(STATUS-DOUT-Pad2)") (class "Default")
      (node (ref "STATUS") (pin "2") (pinfunction "DOUT_2") (pintype "unspecified+no_connect"))
    )
    (net (code "108") (name "unconnected-(U1-CE-Pad9)") (class "Default")
      (node (ref "U1") (pin "9") (pinfunction "CE_9") (pintype "unspecified+no_connect"))
    )
    (net (code "109") (name "unconnected-(U1-DSEL-Pad24)") (class "Default")
      (node (ref "U1") (pin "24") (pinfunction "DSEL_24") (pintype "unspecified+no_connect"))
    )
    (net (code "110") (name "unconnected-(U1-INT-Pad7)") (class "Default")
      (node (ref "U1") (pin "7") (pinfunction "INT_7") (pintype "unspecified+no_connect"))
    )
    (net (code "111") (name "unconnected-(U1-OTG-Pad8)") (class "Default")
      (node (ref "U1") (pin "8") (pinfunction "OTG_8") (pintype "unspecified+no_connect"))
    )
    (net (code "112") (name "unconnected-(U1-QON-Pad12)") (class "Default")
      (node (ref "U1") (pin "12") (pinfunction "QON_12") (pintype "unspecified+no_connect"))
    )
    (net (code "113") (name "unconnected-(VBUS-SBU1-PadA8)") (class "Default")
      (node (ref "VBUS") (pin "A8") (pinfunction "SBU1_A8") (pintype "unspecified+no_connect"))
    )
    (net (code "114") (name "unconnected-(VBUS-SBU2-PadB8)") (class "Default")
      (node (ref "VBUS") (pin "B8") (pinfunction "SBU2_B8") (pintype "unspecified+no_connect"))
    )
    (net (code "115") (name "unconnected-(VBUS-SHIELD-PadSHELL)") (class "Default")
      (node (ref "VBUS") (pin "SHELL") (pinfunction "SHIELD_SHELL") (pintype "unspecified+no_connect"))
    )
    (net (code "116") (name "unconnected-(VBUS-VBUS-PadA4B9)") (class "Default")
      (node (ref "VBUS") (pin "A4B9") (pinfunction "VBUS_A4B9") (pintype "unspecified+no_connect"))
    )
    (net (code "117") (name "unconnected-(VBUS-VBUS-PadB4A9)") (class "Default")
      (node (ref "VBUS") (pin "B4A9") (pinfunction "VBUS_B4A9") (pintype "unspecified+no_connect"))
    )
  )
)
